# NRF24_4.net
KiCad netlist of a schematic drawn in EAGLE
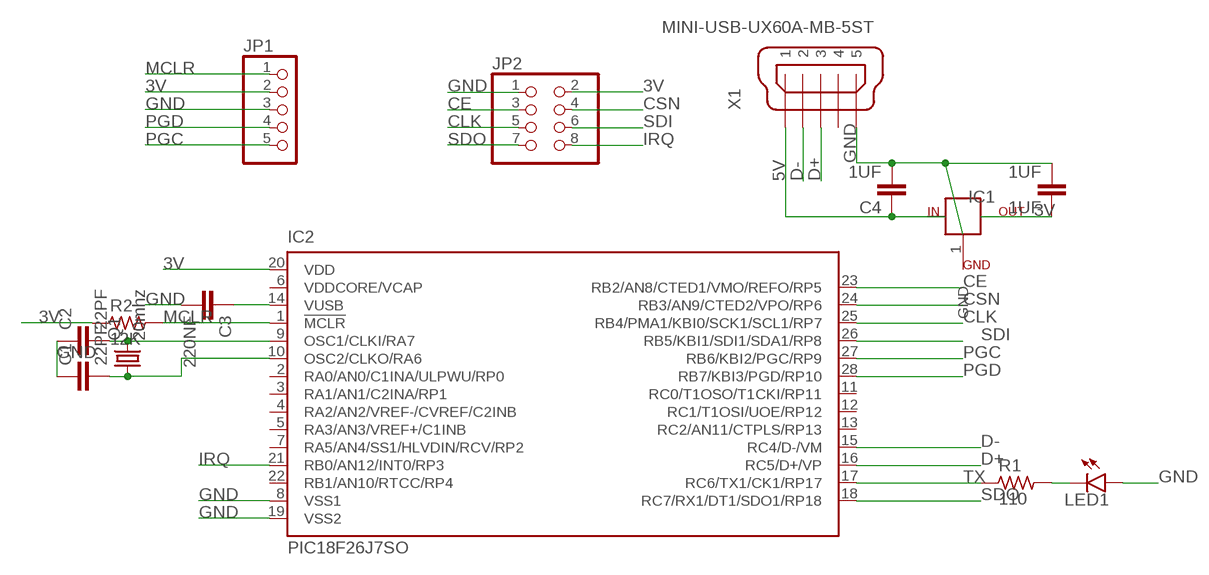
[diagram p0: schematic, sheet 1]

(export (version "E")
  (design (tool "Eeschema 10.0.6"))
  (components
    (comp (ref "1UF")
      (value "1UF")
      (footprint "eagle-import:C025-024X044")
      (libsource (lib "eagle-import") (part "C-EU025-024X044"))
    )
    (comp (ref "C1")
      (value "22PF")
      (footprint "eagle-import:C0805K")
      (libsource (lib "eagle-import") (part "C-EUC0805K"))
    )
    (comp (ref "C2")
      (value "22PF")
      (footprint "eagle-import:C0805K")
      (libsource (lib "eagle-import") (part "C-EUC0805K"))
    )
    (comp (ref "C3")
      (value "220NF")
      (footprint "eagle-import:C0805K")
      (libsource (lib "eagle-import") (part "C-EUC0805K"))
    )
    (comp (ref "C4")
      (value "1UF")
      (footprint "eagle-import:C025-024X044")
      (libsource (lib "eagle-import") (part "C-EU025-024X044"))
    )
    (comp (ref "IC1")
      (value "MCP17")
      (footprint "eagle-import:SOT223")
      (libsource (lib "eagle-import") (part "ZENER-DIODESOT223"))
    )
    (comp (ref "IC2")
      (value "PIC18F26J7SO")
      (footprint "eagle-import:SO28W")
      (fields (field (name "MPN") "PIC18F27J53-I/SO"))
      (libsource (lib "eagle-import") (part "PIC18F26JSO7"))
    )
    (comp (ref "JP1")
      (value "PINHD-1X5")
      (footprint "eagle-import:1X05")
      (libsource (lib "eagle-import") (part "PINHD-1X5"))
    )
    (comp (ref "JP2")
      (value "PINHD-2X4")
      (footprint "eagle-import:2X04")
      (libsource (lib "eagle-import") (part "PINHD-2X4"))
    )
    (comp (ref "LED1")
      (value "LED3MM")
      (footprint "eagle-import:LED3MM")
      (libsource (lib "eagle-import") (part "LED3MM"))
    )
    (comp (ref "Q1")
      (value "20mhz")
      (footprint "eagle-import:HC49_S")
      (libsource (lib "eagle-import") (part "CRYTALHC49S"))
    )
    (comp (ref "R1")
      (value "110")
      (footprint "eagle-import:R0805")
      (libsource (lib "eagle-import") (part "R_0805"))
    )
    (comp (ref "R2")
      (value "12K")
      (footprint "eagle-import:R0805")
      (libsource (lib "eagle-import") (part "R_0805"))
    )
    (comp (ref "X1")
      (value "MINI-USB-UX60A-MB-5ST")
      (footprint "eagle-import:UX60A-MB-5ST")
      (libsource (lib "eagle-import") (part "MINI-USB-UX60A-MB-5ST"))
    )
  )
  (nets
    (net (code "1") (name "/3V") (class "Default")
      (node (ref "1UF") (pin "1") (pinfunction "1_1") (pintype "passive"))
      (node (ref "IC1") (pin "3") (pinfunction "OUT_3") (pintype "passive"))
      (node (ref "IC2") (pin "20") (pinfunction "VDD_20") (pintype "input"))
      (node (ref "JP1") (pin "2") (pinfunction "2_2") (pintype "passive"))
      (node (ref "JP2") (pin "2") (pinfunction "2_2") (pintype "passive"))
      (node (ref "R2") (pin "1") (pinfunction "1_1") (pintype "passive"))
    )
    (net (code "2") (name "/5V") (class "Default")
      (node (ref "C4") (pin "1") (pinfunction "1_1") (pintype "passive"))
      (node (ref "IC1") (pin "2") (pinfunction "IN_2") (pintype "passive"))
      (node (ref "X1") (pin "1") (pinfunction "1_1") (pintype "input"))
    )
    (net (code "3") (name "/CE") (class "Default")
      (node (ref "IC2") (pin "23") (pinfunction "RB2/AN8/CTED1/VMO/REFO/RP5_23") (pintype "bidirectional"))
      (node (ref "JP2") (pin "3") (pinfunction "3_3") (pintype "passive"))
    )
    (net (code "4") (name "/CLK") (class "Default")
      (node (ref "IC2") (pin "25") (pinfunction "RB4/PMA1/KBI0/SCK1/SCL1/RP7_25") (pintype "bidirectional"))
      (node (ref "JP2") (pin "5") (pinfunction "5_5") (pintype "passive"))
    )
    (net (code "5") (name "/CSN") (class "Default")
      (node (ref "IC2") (pin "24") (pinfunction "RB3/AN9/CTED2/VPO/RP6_24") (pintype "bidirectional"))
      (node (ref "JP2") (pin "4") (pinfunction "4_4") (pintype "passive"))
    )
    (net (code "6") (name "/D+") (class "Default")
      (node (ref "IC2") (pin "16") (pinfunction "RC5/D+/VP_16") (pintype "bidirectional"))
      (node (ref "X1") (pin "3") (pinfunction "3_3") (pintype "input"))
    )
    (net (code "7") (name "/D-") (class "Default")
      (node (ref "IC2") (pin "15") (pinfunction "RC4/D-/VM_15") (pintype "bidirectional"))
      (node (ref "X1") (pin "2") (pinfunction "2_2") (pintype "input"))
    )
    (net (code "8") (name "/GND") (class "Default")
      (node (ref "1UF") (pin "2") (pinfunction "2_2") (pintype "passive"))
      (node (ref "C1") (pin "1") (pinfunction "1_1") (pintype "passive"))
      (node (ref "C2") (pin "1") (pinfunction "1_1") (pintype "passive"))
      (node (ref "C3") (pin "2") (pinfunction "2_2") (pintype "passive"))
      (node (ref "C4") (pin "2") (pinfunction "2_2") (pintype "passive"))
      (node (ref "IC1") (pin "1") (pinfunction "GND_1") (pintype "bidirectional"))
      (node (ref "IC2") (pin "19") (pinfunction "VSS2_19") (pintype "input"))
      (node (ref "IC2") (pin "8") (pinfunction "VSS1_8") (pintype "input"))
      (node (ref "JP1") (pin "3") (pinfunction "3_3") (pintype "passive"))
      (node (ref "JP2") (pin "1") (pinfunction "1_1") (pintype "passive"))
      (node (ref "LED1") (pin "A") (pinfunction "ANODE_A") (pintype "passive"))
      (node (ref "X1") (pin "5") (pinfunction "5_5") (pintype "input"))
    )
    (net (code "9") (name "/IRQ") (class "Default")
      (node (ref "IC2") (pin "21") (pinfunction "RB0/AN12/INT0/RP3_21") (pintype "bidirectional"))
      (node (ref "JP2") (pin "8") (pinfunction "8_8") (pintype "passive"))
    )
    (net (code "10") (name "/MCLR") (class "Default")
      (node (ref "IC2") (pin "1") (pinfunction "~{MCLR}_1") (pintype "input"))
      (node (ref "JP1") (pin "1") (pinfunction "1_1") (pintype "passive"))
      (node (ref "R2") (pin "2") (pinfunction "2_2") (pintype "passive"))
    )
    (net (code "11") (name "/PGC") (class "Default")
      (node (ref "IC2") (pin "27") (pinfunction "RB6/KBI2/PGC/RP9_27") (pintype "bidirectional"))
      (node (ref "JP1") (pin "5") (pinfunction "5_5") (pintype "passive"))
    )
    (net (code "12") (name "/PGD") (class "Default")
      (node (ref "IC2") (pin "28") (pinfunction "RB7/KBI3/PGD/RP10_28") (pintype "bidirectional"))
      (node (ref "JP1") (pin "4") (pinfunction "4_4") (pintype "passive"))
    )
    (net (code "13") (name "/SDI") (class "Default")
      (node (ref "IC2") (pin "26") (pinfunction "RB5/KBI1/SDI1/SDA1/RP8_26") (pintype "bidirectional"))
      (node (ref "JP2") (pin "6") (pinfunction "6_6") (pintype "passive"))
    )
    (net (code "14") (name "/SDO") (class "Default")
      (node (ref "IC2") (pin "18") (pinfunction "RC7/RX1/DT1/SDO1/RP18_18") (pintype "bidirectional"))
      (node (ref "JP2") (pin "7") (pinfunction "7_7") (pintype "passive"))
    )
    (net (code "15") (name "/TX") (class "Default")
      (node (ref "IC2") (pin "17") (pinfunction "RC6/TX1/CK1/RP17_17") (pintype "bidirectional"))
      (node (ref "R1") (pin "1") (pinfunction "1_1") (pintype "passive"))
    )
    (net (code "16") (name "Net-(IC2-OSC1{slash}CLKI{slash}RA7)") (class "Default")
      (node (ref "C2") (pin "2") (pinfunction "2_2") (pintype "passive"))
      (node (ref "IC2") (pin "9") (pinfunction "OSC1/CLKI/RA7_9") (pintype "bidirectional"))
      (node (ref "Q1") (pin "2") (pinfunction "2_2") (pintype "passive"))
    )
    (net (code "17") (name "Net-(IC2-OSC2{slash}CLKO{slash}RA6)") (class "Default")
      (node (ref "C1") (pin "2") (pinfunction "2_2") (pintype "passive"))
      (node (ref "IC2") (pin "10") (pinfunction "OSC2/CLKO/RA6_10") (pintype "bidirectional"))
      (node (ref "Q1") (pin "1") (pinfunction "1_1") (pintype "passive"))
    )
    (net (code "18") (name "Net-(IC2-VUSB)") (class "Default")
      (node (ref "C3") (pin "1") (pinfunction "1_1") (pintype "passive"))
      (node (ref "IC2") (pin "14") (pinfunction "VUSB_14") (pintype "input"))
    )
    (net (code "19") (name "Net-(LED1-CATHODE)") (class "Default")
      (node (ref "LED1") (pin "K") (pinfunction "CATHODE_K") (pintype "passive"))
      (node (ref "R1") (pin "2") (pinfunction "2_2") (pintype "passive"))
    )
    (net (code "20") (name "unconnected-(IC2-RA0{slash}AN0{slash}C1INA{slash}ULPWU{slash}RP0-Pad2)") (class "Default")
      (node (ref "IC2") (pin "2") (pinfunction "RA0/AN0/C1INA/ULPWU/RP0_2") (pintype "bidirectional"))
    )
    (net (code "21") (name "unconnected-(IC2-RA1{slash}AN1{slash}C2INA{slash}RP1-Pad3)") (class "Default")
      (node (ref "IC2") (pin "3") (pinfunction "RA1/AN1/C2INA/RP1_3") (pintype "bidirectional"))
    )
    (net (code "22") (name "unconnected-(IC2-RA2{slash}AN2{slash}VREF-{slash}CVREF{slash}C2INB-Pad4)") (class "Default")
      (node (ref "IC2") (pin "4") (pinfunction "RA2/AN2/VREF-/CVREF/C2INB_4") (pintype "bidirectional"))
    )
    (net (code "23") (name "unconnected-(IC2-RA3{slash}AN3{slash}VREF+{slash}C1INB-Pad5)") (class "Default")
      (node (ref "IC2") (pin "5") (pinfunction "RA3/AN3/VREF+/C1INB_5") (pintype "bidirectional"))
    )
    (net (code "24") (name "unconnected-(IC2-RA5{slash}AN4{slash}SS1{slash}HLVDIN{slash}RCV{slash}RP2-Pad7)") (class "Default")
      (node (ref "IC2") (pin "7") (pinfunction "RA5/AN4/SS1/HLVDIN/RCV/RP2_7") (pintype "bidirectional"))
    )
    (net (code "25") (name "unconnected-(IC2-RB1{slash}AN10{slash}RTCC{slash}RP4-Pad22)") (class "Default")
      (node (ref "IC2") (pin "22") (pinfunction "RB1/AN10/RTCC/RP4_22") (pintype "bidirectional"))
    )
    (net (code "26") (name "unconnected-(IC2-RC0{slash}T1OSO{slash}T1CKI{slash}RP11-Pad11)") (class "Default")
      (node (ref "IC2") (pin "11") (pinfunction "RC0/T1OSO/T1CKI/RP11_11") (pintype "bidirectional"))
    )
    (net (code "27") (name "unconnected-(IC2-RC1{slash}T1OSI{slash}UOE{slash}RP12-Pad12)") (class "Default")
      (node (ref "IC2") (pin "12") (pinfunction "RC1/T1OSI/UOE/RP12_12") (pintype "bidirectional"))
    )
    (net (code "28") (name "unconnected-(IC2-RC2{slash}AN11{slash}CTPLS{slash}RP13-Pad13)") (class "Default")
      (node (ref "IC2") (pin "13") (pinfunction "RC2/AN11/CTPLS/RP13_13") (pintype "bidirectional"))
    )
    (net (code "29") (name "unconnected-(IC2-VDDCORE{slash}VCAP-Pad6)") (class "Default")
      (node (ref "IC2") (pin "6") (pinfunction "VDDCORE/VCAP_6") (pintype "input"))
    )
    (net (code "30") (name "unconnected-(X1-Pad4)") (class "Default")
      (node (ref "X1") (pin "4") (pinfunction "4_4") (pintype "input"))
    )
  )
)
